# design.net
KiCad netlist of a schematic drawn in Altium Designer
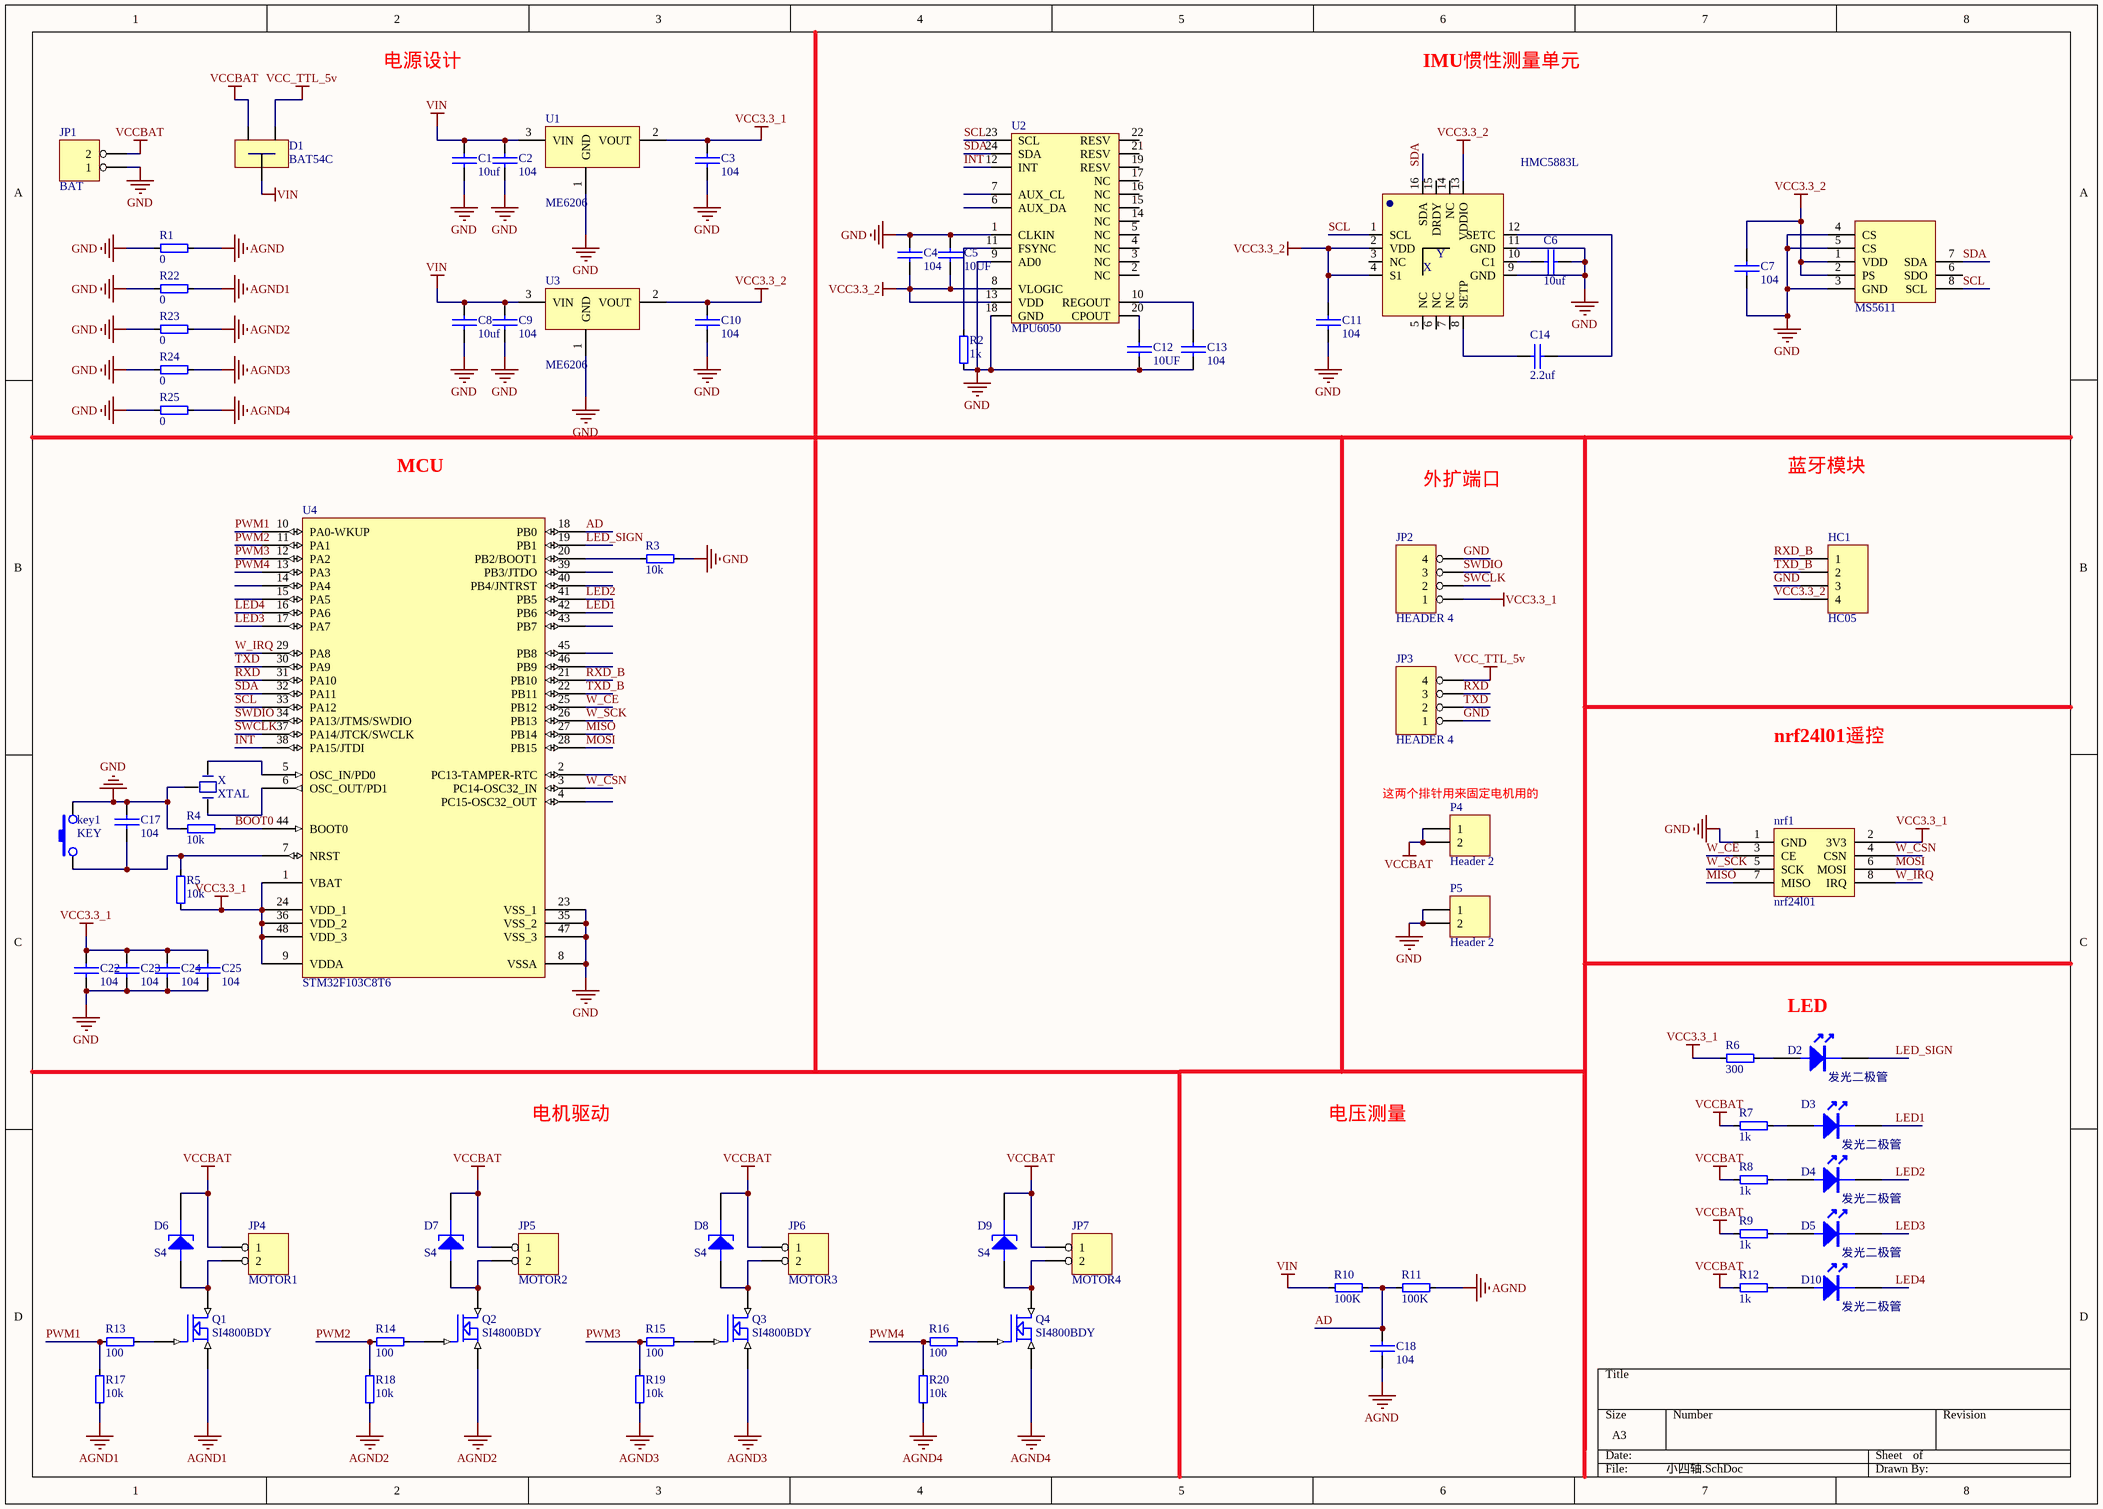
[diagram p0: 小四轴.SchDoc]

(export (version "E")
  (design (tool "Eeschema 10.0.6"))
  (components
    (comp (ref "*1") (value "HMC5883L") (footprint "hmc5883l") (libsource (lib "我的元件") (part "HMC5883L")))
    (comp (ref "arctory1") (value "MS5611") (footprint "MS5611") (libsource (lib "常用元件库") (part "MS5611")))
    (comp (ref "C1")
      (value "10uf")
      (footprint "0603P")
      (description "Capacitor")
      (libsource (lib "电容") (part "C_N"))
    )
    (comp (ref "C2")
      (value "104")
      (footprint "0603P")
      (description "Capacitor")
      (libsource (lib "电容") (part "C_N"))
    )
    (comp (ref "C3")
      (value "104")
      (footprint "0603P")
      (description "Capacitor")
      (libsource (lib "电容") (part "C_N"))
    )
    (comp (ref "C4")
      (value "104")
      (footprint "0603P")
      (description "Capacitor")
      (libsource (lib "电容") (part "C_N"))
    )
    (comp (ref "C5")
      (value "10UF")
      (footprint "0603P")
      (description "Capacitor")
      (libsource (lib "电容") (part "C_N"))
    )
    (comp (ref "C6")
      (value "10uf")
      (footprint "0603P")
      (description "Capacitor")
      (libsource (lib "电容") (part "C_N"))
    )
    (comp (ref "C7")
      (value "104")
      (footprint "0603p")
      (description "Capacitor")
      (libsource (lib "电容") (part "C_N"))
    )
    (comp (ref "C8")
      (value "10uf")
      (footprint "0603P")
      (description "Capacitor")
      (libsource (lib "电容") (part "C_N"))
    )
    (comp (ref "C9")
      (value "104")
      (footprint "0603P")
      (description "Capacitor")
      (libsource (lib "电容") (part "C_N"))
    )
    (comp (ref "C10")
      (value "104")
      (footprint "0603P")
      (description "Capacitor")
      (libsource (lib "电容") (part "C_N"))
    )
    (comp (ref "C11")
      (value "104")
      (footprint "0603P")
      (description "Capacitor")
      (libsource (lib "电容") (part "C_N"))
    )
    (comp (ref "C12")
      (value "10UF")
      (footprint "0603P")
      (description "Capacitor")
      (libsource (lib "电容") (part "C_N"))
    )
    (comp (ref "C13")
      (value "104")
      (footprint "0603P")
      (description "Capacitor")
      (libsource (lib "电容") (part "C_N"))
    )
    (comp (ref "C14")
      (value "2.2uf")
      (footprint "0603P")
      (description "Capacitor")
      (libsource (lib "电容") (part "C_N"))
    )
    (comp (ref "C17")
      (value "104")
      (footprint "0603P")
      (description "Capacitor")
      (libsource (lib "电容") (part "C_N"))
    )
    (comp (ref "C18")
      (value "104")
      (footprint "0603P")
      (description "Capacitor")
      (libsource (lib "电容") (part "C_N"))
    )
    (comp (ref "C22")
      (value "104")
      (footprint "0603P")
      (description "Capacitor")
      (libsource (lib "电容") (part "C_N"))
    )
    (comp (ref "C23")
      (value "104")
      (footprint "0603P")
      (description "Capacitor")
      (libsource (lib "电容") (part "C_N"))
    )
    (comp (ref "C24")
      (value "104")
      (footprint "0603P")
      (description "Capacitor")
      (libsource (lib "电容") (part "C_N"))
    )
    (comp (ref "C25")
      (value "104")
      (footprint "0603P")
      (description "Capacitor")
      (libsource (lib "电容") (part "C_N"))
    )
    (comp (ref "D1") (value "BAT54C") (footprint "SOT23") (libsource (lib "二极管") (part "BAT54C")))
    (comp (ref "D2") (value "发光二极管") (footprint "0805") (libsource (lib "二极管") (part "发光二极管")))
    (comp (ref "D3") (value "发光二极管") (footprint "0805") (libsource (lib "二极管") (part "发光二极管")))
    (comp (ref "D4") (value "发光二极管") (footprint "0805") (libsource (lib "二极管") (part "发光二极管")))
    (comp (ref "D5") (value "发光二极管") (footprint "0805") (libsource (lib "二极管") (part "发光二极管")))
    (comp (ref "D6")
      (value "S4")
      (footprint "LC-SOD-123")
      (description "Tunnel FDiode")
      (libsource (lib "二极管") (part "TUNNEL"))
    )
    (comp (ref "D7")
      (value "S4")
      (footprint "LC-SOD-123")
      (description "Tunnel FDiode")
      (libsource (lib "二极管") (part "TUNNEL"))
    )
    (comp (ref "D8")
      (value "S4")
      (footprint "LC-SOD-123")
      (description "Tunnel FDiode")
      (libsource (lib "二极管") (part "TUNNEL"))
    )
    (comp (ref "D9")
      (value "S4")
      (footprint "LC-SOD-123")
      (description "Tunnel FDiode")
      (libsource (lib "二极管") (part "TUNNEL"))
    )
    (comp (ref "D10") (value "发光二极管") (footprint "0805") (libsource (lib "二极管") (part "发光二极管")))
    (comp (ref "HC1")
      (value "HC05")
      (footprint "HDR1X4")
      (description "Header, 4-Pin")
      (fields (field (name "PUBLISHER") "Altium Limited"))
      (libsource (lib "Explorer STM32F407封装库") (part "Header 4"))
    )
    (comp (ref "JP1") (value "BAT") (footprint "HDR1X2") (libsource (lib "") (part "HEADER 2_1")))
    (comp (ref "JP2")
      (value "HEADER 4")
      (footprint "HDR1X4")
      (description "4 Pin Header")
      (libsource (lib "杂元件库") (part "HEADER 4"))
    )
    (comp (ref "JP3")
      (value "HEADER 4")
      (footprint "HDR1X4")
      (description "4 Pin Header")
      (libsource (lib "杂元件库") (part "HEADER 4"))
    )
    (comp (ref "JP4") (value "MOTOR1") (footprint "HDR1X2") (libsource (lib "杂元件库") (part "HEADER 2")))
    (comp (ref "JP5") (value "MOTOR2") (footprint "HDR1X2") (libsource (lib "杂元件库") (part "HEADER 2")))
    (comp (ref "JP6") (value "MOTOR3") (footprint "HDR1X2") (libsource (lib "杂元件库") (part "HEADER 2")))
    (comp (ref "JP7") (value "MOTOR4") (footprint "HDR1X2") (libsource (lib "杂元件库") (part "HEADER 2")))
    (comp (ref "key1") (value "KEY") (footprint "贴片按键6.1x3.7") (libsource (lib "常用元件库") (part "KEY")))
    (comp (ref "nrf1") (value "nrf24l01") (footprint "HDR2X4") (libsource (lib "常用元件库") (part "nrf24l01")))
    (comp (ref "P4")
      (value "Header 2")
      (footprint "HDR1X2")
      (description "Header, 2-Pin")
      (fields (field (name "PUBLISHER") "Altium Limited"))
      (libsource (lib "Miscellaneous Connectors") (part "Header 2"))
    )
    (comp (ref "P5")
      (value "Header 2")
      (footprint "HDR1X2")
      (description "Header, 2-Pin")
      (fields (field (name "PUBLISHER") "Altium Limited"))
      (libsource (lib "Miscellaneous Connectors") (part "Header 2"))
    )
    (comp (ref "Q1")
      (value "SI4800BDY")
      (footprint "LC-SOIC-8_150mil")
      (libsource (lib "Miscellaneous Devices") (part "MOSFET N"))
    )
    (comp (ref "Q2")
      (value "SI4800BDY")
      (footprint "LC-SOIC-8_150mil")
      (libsource (lib "Miscellaneous Devices") (part "MOSFET N"))
    )
    (comp (ref "Q3")
      (value "SI4800BDY")
      (footprint "LC-SOIC-8_150mil")
      (libsource (lib "Miscellaneous Devices") (part "MOSFET N"))
    )
    (comp (ref "Q4")
      (value "SI4800BDY")
      (footprint "LC-SOIC-8_150mil")
      (libsource (lib "Miscellaneous Devices") (part "MOSFET N"))
    )
    (comp (ref "R1") (value "0") (footprint "0603P") (libsource (lib "电阻") (part "RES")))
    (comp (ref "R2") (value "1k") (footprint "0603P") (libsource (lib "电阻") (part "RES")))
    (comp (ref "R3") (value "10k") (footprint "0603P") (libsource (lib "电阻") (part "RES")))
    (comp (ref "R4") (value "10k") (footprint "0603P") (libsource (lib "电阻") (part "RES")))
    (comp (ref "R5") (value "10k") (footprint "0603P") (libsource (lib "电阻") (part "RES")))
    (comp (ref "R6") (value "300") (footprint "0603P") (libsource (lib "电阻") (part "RES")))
    (comp (ref "R7") (value "1k") (footprint "0603P") (libsource (lib "电阻") (part "RES")))
    (comp (ref "R8") (value "1k") (footprint "0603P") (libsource (lib "电阻") (part "RES")))
    (comp (ref "R9") (value "1k") (footprint "0603P") (libsource (lib "电阻") (part "RES")))
    (comp (ref "R10") (value "100K") (footprint "0603P") (libsource (lib "电阻") (part "RES")))
    (comp (ref "R11") (value "100K") (footprint "0603P") (libsource (lib "电阻") (part "RES")))
    (comp (ref "R12") (value "1k") (footprint "0603P") (libsource (lib "电阻") (part "RES")))
    (comp (ref "R13") (value "100") (footprint "0603P") (libsource (lib "电阻") (part "RES")))
    (comp (ref "R14") (value "100") (footprint "0603P") (libsource (lib "电阻") (part "RES")))
    (comp (ref "R15") (value "100") (footprint "0603P") (libsource (lib "电阻") (part "RES")))
    (comp (ref "R16") (value "100") (footprint "0603P") (libsource (lib "电阻") (part "RES")))
    (comp (ref "R17") (value "10k") (footprint "0603P") (libsource (lib "电阻") (part "RES")))
    (comp (ref "R18") (value "10k") (footprint "0603P") (libsource (lib "电阻") (part "RES")))
    (comp (ref "R19") (value "10k") (footprint "0603P") (libsource (lib "电阻") (part "RES")))
    (comp (ref "R20") (value "10k") (footprint "0603P") (libsource (lib "电阻") (part "RES")))
    (comp (ref "R22") (value "0") (footprint "0603P") (libsource (lib "电阻") (part "RES")))
    (comp (ref "R23") (value "0") (footprint "0603P") (libsource (lib "电阻") (part "RES")))
    (comp (ref "R24") (value "0") (footprint "0603P") (libsource (lib "电阻") (part "RES")))
    (comp (ref "R25") (value "0") (footprint "0603P") (libsource (lib "电阻") (part "RES")))
    (comp (ref "U1") (value "ME6206") (footprint "ME6206") (libsource (lib "我的元件") (part "ME6206")))
    (comp (ref "U2")
      (value "MPU6050")
      (footprint "QFN24")
      (description "9轴运动处理传感器")
      (libsource (lib "Explorer STM32F407封装库") (part "MPU6050"))
    )
    (comp (ref "U3") (value "ME6206") (footprint "ME6206") (libsource (lib "我的元件") (part "ME6206")))
    (comp (ref "U4")
      (value "STM32F103C8T6")
      (footprint "LQFP48_N")
      (description "STM32 ARM-based 32-bit MCU with 64 Kbytes Flash, 48-pin LQFP, Industrial Temperature")
      (fields (field (name "PUBLISHER") "*"))
      (libsource (lib "STM32 SCH") (part "STM32F103C8T6"))
    )
    (comp (ref "X") (value "XTAL") (footprint "三脚晶振") (libsource (lib "常用元件库") (part "XTAL_3P")))
  )
  (nets
    (net (code "1") (name "/AD") (class "Default")
      (node (ref "C18") (pin "2") (pinfunction "2_2") (pintype "passive"))
      (node (ref "R10") (pin "1") (pinfunction "1_1") (pintype "passive"))
      (node (ref "R11") (pin "2") (pinfunction "2_2") (pintype "passive"))
      (node (ref "U4") (pin "18") (pinfunction "PB0_18") (pintype "bidirectional"))
    )
    (net (code "2") (name "/BOOT0") (class "Default")
      (node (ref "R4") (pin "2") (pinfunction "2_2") (pintype "passive"))
      (node (ref "U4") (pin "44") (pinfunction "BOOT0_44") (pintype "input"))
    )
    (net (code "3") (name "/INT") (class "Default")
      (node (ref "U2") (pin "12") (pinfunction "INT_12") (pintype "passive"))
      (node (ref "U4") (pin "38") (pinfunction "PA15/JTDI_38") (pintype "bidirectional"))
    )
    (net (code "4") (name "/LED1") (class "Default")
      (node (ref "D3") (pin "2") (pinfunction "2_2") (pintype "passive"))
      (node (ref "U4") (pin "42") (pinfunction "PB6_42") (pintype "bidirectional"))
    )
    (net (code "5") (name "/LED2") (class "Default")
      (node (ref "D4") (pin "2") (pinfunction "2_2") (pintype "passive"))
      (node (ref "U4") (pin "41") (pinfunction "PB5_41") (pintype "bidirectional"))
    )
    (net (code "6") (name "/LED3") (class "Default")
      (node (ref "D5") (pin "2") (pinfunction "2_2") (pintype "passive"))
      (node (ref "U4") (pin "17") (pinfunction "PA7_17") (pintype "bidirectional"))
    )
    (net (code "7") (name "/LED4") (class "Default")
      (node (ref "D10") (pin "2") (pinfunction "2_2") (pintype "passive"))
      (node (ref "U4") (pin "16") (pinfunction "PA6_16") (pintype "bidirectional"))
    )
    (net (code "8") (name "/LED_SIGN") (class "Default")
      (node (ref "D2") (pin "2") (pinfunction "2_2") (pintype "passive"))
      (node (ref "U4") (pin "19") (pinfunction "PB1_19") (pintype "bidirectional"))
    )
    (net (code "9") (name "/MISO") (class "Default")
      (node (ref "U4") (pin "27") (pinfunction "PB14_27") (pintype "bidirectional"))
      (node (ref "nrf1") (pin "7") (pinfunction "MISO_7") (pintype "passive"))
    )
    (net (code "10") (name "/MOSI") (class "Default")
      (node (ref "U4") (pin "28") (pinfunction "PB15_28") (pintype "bidirectional"))
      (node (ref "nrf1") (pin "6") (pinfunction "MOSI_6") (pintype "passive"))
    )
    (net (code "11") (name "/PWM1") (class "Default")
      (node (ref "R13") (pin "2") (pinfunction "2_2") (pintype "passive"))
      (node (ref "R17") (pin "1") (pinfunction "1_1") (pintype "passive"))
      (node (ref "U4") (pin "10") (pinfunction "PA0-WKUP_10") (pintype "bidirectional"))
    )
    (net (code "12") (name "/PWM2") (class "Default")
      (node (ref "R14") (pin "2") (pinfunction "2_2") (pintype "passive"))
      (node (ref "R18") (pin "1") (pinfunction "1_1") (pintype "passive"))
      (node (ref "U4") (pin "11") (pinfunction "PA1_11") (pintype "bidirectional"))
    )
    (net (code "13") (name "/PWM3") (class "Default")
      (node (ref "R15") (pin "2") (pinfunction "2_2") (pintype "passive"))
      (node (ref "R19") (pin "1") (pinfunction "1_1") (pintype "passive"))
      (node (ref "U4") (pin "12") (pinfunction "PA2_12") (pintype "bidirectional"))
    )
    (net (code "14") (name "/PWM4") (class "Default")
      (node (ref "R16") (pin "2") (pinfunction "2_2") (pintype "passive"))
      (node (ref "R20") (pin "1") (pinfunction "1_1") (pintype "passive"))
      (node (ref "U4") (pin "13") (pinfunction "PA3_13") (pintype "bidirectional"))
    )
    (net (code "15") (name "/RXD") (class "Default")
      (node (ref "JP3") (pin "3") (pinfunction "3_3") (pintype "passive"))
      (node (ref "U4") (pin "31") (pinfunction "PA10_31") (pintype "bidirectional"))
    )
    (net (code "16") (name "/RXD_B") (class "Default")
      (node (ref "HC1") (pin "1") (pinfunction "1_1") (pintype "passive"))
      (node (ref "U4") (pin "21") (pinfunction "PB10_21") (pintype "bidirectional"))
    )
    (net (code "17") (name "/SCL") (class "Default")
      (node (ref "*1") (pin "1") (pinfunction "SCL_1") (pintype "passive"))
      (node (ref "U2") (pin "23") (pinfunction "SCL_23") (pintype "passive"))
      (node (ref "U4") (pin "33") (pinfunction "PA12_33") (pintype "bidirectional"))
      (node (ref "arctory1") (pin "8") (pinfunction "SCL_8") (pintype "passive"))
    )
    (net (code "18") (name "/SDA") (class "Default")
      (node (ref "*1") (pin "16") (pinfunction "SDA_16") (pintype "passive"))
      (node (ref "U2") (pin "24") (pinfunction "SDA_24") (pintype "passive"))
      (node (ref "U4") (pin "32") (pinfunction "PA11_32") (pintype "bidirectional"))
      (node (ref "arctory1") (pin "7") (pinfunction "SDA_7") (pintype "passive"))
    )
    (net (code "19") (name "/SWCLK") (class "Default")
      (node (ref "JP2") (pin "2") (pinfunction "2_2") (pintype "passive"))
      (node (ref "U4") (pin "37") (pinfunction "PA14/JTCK/SWCLK_37") (pintype "bidirectional"))
    )
    (net (code "20") (name "/SWDIO") (class "Default")
      (node (ref "JP2") (pin "3") (pinfunction "3_3") (pintype "passive"))
      (node (ref "U4") (pin "34") (pinfunction "PA13/JTMS/SWDIO_34") (pintype "bidirectional"))
    )
    (net (code "21") (name "/TXD") (class "Default")
      (node (ref "JP3") (pin "2") (pinfunction "2_2") (pintype "passive"))
      (node (ref "U4") (pin "30") (pinfunction "PA9_30") (pintype "bidirectional"))
    )
    (net (code "22") (name "/TXD_B") (class "Default")
      (node (ref "HC1") (pin "2") (pinfunction "2_2") (pintype "passive"))
      (node (ref "U4") (pin "22") (pinfunction "PB11_22") (pintype "bidirectional"))
    )
    (net (code "23") (name "/W_CE") (class "Default")
      (node (ref "U4") (pin "25") (pinfunction "PB12_25") (pintype "bidirectional"))
      (node (ref "nrf1") (pin "3") (pinfunction "CE_3") (pintype "passive"))
    )
    (net (code "24") (name "/W_CSN") (class "Default")
      (node (ref "U4") (pin "3") (pinfunction "PC14-OSC32_IN_3") (pintype "bidirectional"))
      (node (ref "nrf1") (pin "4") (pinfunction "CSN_4") (pintype "passive"))
    )
    (net (code "25") (name "/W_IRQ") (class "Default")
      (node (ref "U4") (pin "29") (pinfunction "PA8_29") (pintype "bidirectional"))
      (node (ref "nrf1") (pin "8") (pinfunction "IRQ_8") (pintype "passive"))
    )
    (net (code "26") (name "/W_SCK") (class "Default")
      (node (ref "U4") (pin "26") (pinfunction "PB13_26") (pintype "bidirectional"))
      (node (ref "nrf1") (pin "5") (pinfunction "SCK_5") (pintype "passive"))
    )
    (net (code "27") (name "AGND") (class "Default")
      (node (ref "C18") (pin "1") (pinfunction "1_1") (pintype "passive"))
      (node (ref "R1") (pin "1") (pinfunction "1_1") (pintype "passive"))
      (node (ref "R11") (pin "1") (pinfunction "1_1") (pintype "passive"))
    )
    (net (code "28") (name "AGND1") (class "Default")
      (node (ref "Q1") (pin "3") (pinfunction "S_3") (pintype "input"))
      (node (ref "R17") (pin "2") (pinfunction "2_2") (pintype "passive"))
      (node (ref "R22") (pin "1") (pinfunction "1_1") (pintype "passive"))
    )
    (net (code "29") (name "AGND2") (class "Default")
      (node (ref "Q2") (pin "3") (pinfunction "S_3") (pintype "input"))
      (node (ref "R18") (pin "2") (pinfunction "2_2") (pintype "passive"))
      (node (ref "R23") (pin "1") (pinfunction "1_1") (pintype "passive"))
    )
    (net (code "30") (name "AGND3") (class "Default")
      (node (ref "Q3") (pin "3") (pinfunction "S_3") (pintype "input"))
      (node (ref "R19") (pin "2") (pinfunction "2_2") (pintype "passive"))
      (node (ref "R24") (pin "1") (pinfunction "1_1") (pintype "passive"))
    )
    (net (code "31") (name "AGND4") (class "Default")
      (node (ref "Q4") (pin "3") (pinfunction "S_3") (pintype "input"))
      (node (ref "R20") (pin "2") (pinfunction "2_2") (pintype "passive"))
      (node (ref "R25") (pin "1") (pinfunction "1_1") (pintype "passive"))
    )
    (net (code "32") (name "GND") (class "Default")
      (node (ref "*1") (pin "11") (pinfunction "GND_11") (pintype "passive"))
      (node (ref "*1") (pin "9") (pinfunction "GND_9") (pintype "passive"))
      (node (ref "C1") (pin "1") (pinfunction "1_1") (pintype "passive"))
      (node (ref "C10") (pin "1") (pinfunction "1_1") (pintype "passive"))
      (node (ref "C11") (pin "2") (pinfunction "2_2") (pintype "passive"))
      (node (ref "C12") (pin "1") (pinfunction "1_1") (pintype "passive"))
      (node (ref "C13") (pin "2") (pinfunction "2_2") (pintype "passive"))
      (node (ref "C17") (pin "1") (pinfunction "1_1") (pintype "passive"))
      (node (ref "C2") (pin "1") (pinfunction "1_1") (pintype "passive"))
      (node (ref "C22") (pin "1") (pinfunction "1_1") (pintype "passive"))
      (node (ref "C23") (pin "1") (pinfunction "1_1") (pintype "passive"))
      (node (ref "C24") (pin "1") (pinfunction "1_1") (pintype "passive"))
      (node (ref "C25") (pin "1") (pinfunction "1_1") (pintype "passive"))
      (node (ref "C3") (pin "1") (pinfunction "1_1") (pintype "passive"))
      (node (ref "C4") (pin "1") (pinfunction "1_1") (pintype "passive"))
      (node (ref "C5") (pin "2") (pinfunction "2_2") (pintype "passive"))
      (node (ref "C6") (pin "2") (pinfunction "2_2") (pintype "passive"))
      (node (ref "C7") (pin "2") (pinfunction "2_2") (pintype "passive"))
      (node (ref "C8") (pin "1") (pinfunction "1_1") (pintype "passive"))
      (node (ref "C9") (pin "1") (pinfunction "1_1") (pintype "passive"))
      (node (ref "HC1") (pin "3") (pinfunction "3_3") (pintype "passive"))
      (node (ref "JP1") (pin "1") (pinfunction "1_1") (pintype "passive"))
      (node (ref "JP2") (pin "4") (pinfunction "4_4") (pintype "passive"))
      (node (ref "JP3") (pin "1") (pinfunction "1_1") (pintype "passive"))
      (node (ref "P5") (pin "1") (pinfunction "1_1") (pintype "passive"))
      (node (ref "P5") (pin "2") (pinfunction "2_2") (pintype "passive"))
      (node (ref "R1") (pin "2") (pinfunction "2_2") (pintype "passive"))
      (node (ref "R2") (pin "1") (pinfunction "1_1") (pintype "passive"))
      (node (ref "R22") (pin "2") (pinfunction "2_2") (pintype "passive"))
      (node (ref "R23") (pin "2") (pinfunction "2_2") (pintype "passive"))
      (node (ref "R24") (pin "2") (pinfunction "2_2") (pintype "passive"))
      (node (ref "R25") (pin "2") (pinfunction "2_2") (pintype "passive"))
      (node (ref "R3") (pin "1") (pinfunction "1_1") (pintype "passive"))
      (node (ref "R4") (pin "1") (pinfunction "1_1") (pintype "passive"))
      (node (ref "U1") (pin "1") (pinfunction "GND_1") (pintype "passive"))
      (node (ref "U2") (pin "1") (pinfunction "CLKIN_1") (pintype "passive"))
      (node (ref "U2") (pin "18") (pinfunction "GND_18") (pintype "passive"))
      (node (ref "U2") (pin "9") (pinfunction "AD0_9") (pintype "passive"))
      (node (ref "U3") (pin "1") (pinfunction "GND_1") (pintype "passive"))
      (node (ref "U4") (pin "23") (pinfunction "VSS_1_23") (pintype "power_in"))
      (node (ref "U4") (pin "35") (pinfunction "VSS_2_35") (pintype "power_in"))
      (node (ref "U4") (pin "47") (pinfunction "VSS_3_47") (pintype "power_in"))
      (node (ref "U4") (pin "8") (pinfunction "VSSA_8") (pintype "power_in"))
      (node (ref "X") (pin "3") (pinfunction "3_3") (pintype "passive"))
      (node (ref "arctory1") (pin "3") (pinfunction "GND_3") (pintype "passive"))
      (node (ref "arctory1") (pin "4") (pinfunction "CS_4") (pintype "passive"))
      (node (ref "arctory1") (pin "5") (pinfunction "CS_5") (pintype "passive"))
      (node (ref "key1") (pin "2") (pinfunction "2_2") (pintype "passive"))
      (node (ref "nrf1") (pin "1") (pinfunction "GND_1") (pintype "passive"))
    )
    (net (code "33") (name "Net-(*1-C1)") (class "Default")
      (node (ref "*1") (pin "10") (pinfunction "C1_10") (pintype "passive"))
      (node (ref "C6") (pin "1") (pinfunction "1_1") (pintype "passive"))
    )
    (net (code "34") (name "Net-(*1-SETC)") (class "Default")
      (node (ref "*1") (pin "12") (pinfunction "SETC_12") (pintype "passive"))
      (node (ref "C14") (pin "2") (pinfunction "2_2") (pintype "passive"))
    )
    (net (code "35") (name "Net-(*1-SETP)") (class "Default")
      (node (ref "*1") (pin "8") (pinfunction "SETP_8") (pintype "passive"))
      (node (ref "C14") (pin "1") (pinfunction "1_1") (pintype "passive"))
    )
    (net (code "36") (name "Net-(D2-Pad1)") (class "Default")
      (node (ref "D2") (pin "1") (pinfunction "1_1") (pintype "passive"))
      (node (ref "R6") (pin "1") (pinfunction "1_1") (pintype "passive"))
    )
    (net (code "37") (name "Net-(D3-Pad1)") (class "Default")
      (node (ref "D3") (pin "1") (pinfunction "1_1") (pintype "passive"))
      (node (ref "R7") (pin "1") (pinfunction "1_1") (pintype "passive"))
    )
    (net (code "38") (name "Net-(D4-Pad1)") (class "Default")
      (node (ref "D4") (pin "1") (pinfunction "1_1") (pintype "passive"))
      (node (ref "R8") (pin "1") (pinfunction "1_1") (pintype "passive"))
    )
    (net (code "39") (name "Net-(D5-Pad1)") (class "Default")
      (node (ref "D5") (pin "1") (pinfunction "1_1") (pintype "passive"))
      (node (ref "R9") (pin "1") (pinfunction "1_1") (pintype "passive"))
    )
    (net (code "40") (name "Net-(D6-A)") (class "Default")
      (node (ref "D6") (pin "1") (pinfunction "A_1") (pintype "passive"))
      (node (ref "JP4") (pin "2") (pinfunction "2_2") (pintype "passive"))
      (node (ref "Q1") (pin "2") (pinfunction "D_2") (pintype "input"))
    )
    (net (code "41") (name "Net-(D7-A)") (class "Default")
      (node (ref "D7") (pin "1") (pinfunction "A_1") (pintype "passive"))
      (node (ref "JP5") (pin "2") (pinfunction "2_2") (pintype "passive"))
      (node (ref "Q2") (pin "2") (pinfunction "D_2") (pintype "input"))
    )
    (net (code "42") (name "Net-(D8-A)") (class "Default")
      (node (ref "D8") (pin "1") (pinfunction "A_1") (pintype "passive"))
      (node (ref "JP6") (pin "2") (pinfunction "2_2") (pintype "passive"))
      (node (ref "Q3") (pin "2") (pinfunction "D_2") (pintype "input"))
    )
    (net (code "43") (name "Net-(D9-A)") (class "Default")
      (node (ref "D9") (pin "1") (pinfunction "A_1") (pintype "passive"))
      (node (ref "JP7") (pin "2") (pinfunction "2_2") (pintype "passive"))
      (node (ref "Q4") (pin "2") (pinfunction "D_2") (pintype "input"))
    )
    (net (code "44") (name "Net-(D10-Pad1)") (class "Default")
      (node (ref "D10") (pin "1") (pinfunction "1_1") (pintype "passive"))
      (node (ref "R12") (pin "1") (pinfunction "1_1") (pintype "passive"))
    )
    (net (code "45") (name "Net-(Q1-G)") (class "Default")
      (node (ref "Q1") (pin "1") (pinfunction "G_1") (pintype "input"))
      (node (ref "R13") (pin "1") (pinfunction "1_1") (pintype "passive"))
    )
    (net (code "46") (name "Net-(Q2-G)") (class "Default")
      (node (ref "Q2") (pin "1") (pinfunction "G_1") (pintype "input"))
      (node (ref "R14") (pin "1") (pinfunction "1_1") (pintype "passive"))
    )
    (net (code "47") (name "Net-(Q3-G)") (class "Default")
      (node (ref "Q3") (pin "1") (pinfunction "G_1") (pintype "input"))
      (node (ref "R15") (pin "1") (pinfunction "1_1") (pintype "passive"))
    )
    (net (code "48") (name "Net-(Q4-G)") (class "Default")
      (node (ref "Q4") (pin "1") (pinfunction "G_1") (pintype "input"))
      (node (ref "R16") (pin "1") (pinfunction "1_1") (pintype "passive"))
    )
    (net (code "49") (name "Net-(U2-CPOUT)") (class "Default")
      (node (ref "C12") (pin "2") (pinfunction "2_2") (pintype "passive"))
      (node (ref "U2") (pin "20") (pinfunction "CPOUT_20") (pintype "passive"))
    )
    (net (code "50") (name "Net-(U2-FSYNC)") (class "Default")
      (node (ref "R2") (pin "2") (pinfunction "2_2") (pintype "passive"))
      (node (ref "U2") (pin "11") (pinfunction "FSYNC_11") (pintype "passive"))
    )
    (net (code "51") (name "Net-(U2-REGOUT)") (class "Default")
      (node (ref "C13") (pin "1") (pinfunction "1_1") (pintype "passive"))
      (node (ref "U2") (pin "10") (pinfunction "REGOUT_10") (pintype "passive"))
    )
    (net (code "52") (name "Net-(U4-NRST)") (class "Default")
      (node (ref "C17") (pin "2") (pinfunction "2_2") (pintype "passive"))
      (node (ref "R5") (pin "1") (pinfunction "1_1") (pintype "passive"))
      (node (ref "U4") (pin "7") (pinfunction "NRST_7") (pintype "bidirectional"))
      (node (ref "key1") (pin "1") (pinfunction "1_1") (pintype "passive"))
    )
    (net (code "53") (name "Net-(U4-OSC_IN{slash}PD0)") (class "Default")
      (node (ref "U4") (pin "5") (pinfunction "OSC_IN/PD0_5") (pintype "input"))
      (node (ref "X") (pin "1") (pinfunction "1_1") (pintype "passive"))
    )
    (net (code "54") (name "Net-(U4-OSC_OUT{slash}PD1)") (class "Default")
      (node (ref "U4") (pin "6") (pinfunction "OSC_OUT/PD1_6") (pintype "output"))
      (node (ref "X") (pin "2") (pinfunction "2_2") (pintype "passive"))
    )
    (net (code "55") (name "Net-(U4-PB2{slash}BOOT1)") (class "Default")
      (node (ref "R3") (pin "2") (pinfunction "2_2") (pintype "passive"))
      (node (ref "U4") (pin "20") (pinfunction "PB2/BOOT1_20") (pintype "bidirectional"))
    )
    (net (code "56") (name "VCC3.3_1") (class "Default")
      (node (ref "C22") (pin "2") (pinfunction "2_2") (pintype "passive"))
      (node (ref "C23") (pin "2") (pinfunction "2_2") (pintype "passive"))
      (node (ref "C24") (pin "2") (pinfunction "2_2") (pintype "passive"))
      (node (ref "C25") (pin "2") (pinfunction "2_2") (pintype "passive"))
      (node (ref "C3") (pin "2") (pinfunction "2_2") (pintype "passive"))
      (node (ref "JP2") (pin "1") (pinfunction "1_1") (pintype "passive"))
      (node (ref "R5") (pin "2") (pinfunction "2_2") (pintype "passive"))
      (node (ref "R6") (pin "2") (pinfunction "2_2") (pintype "passive"))
      (node (ref "U1") (pin "2") (pinfunction "VOUT_2") (pintype "passive"))
      (node (ref "U4") (pin "1") (pinfunction "VBAT_1") (pintype "power_in"))
      (node (ref "U4") (pin "24") (pinfunction "VDD_1_24") (pintype "power_in"))
      (node (ref "U4") (pin "36") (pinfunction "VDD_2_36") (pintype "power_in"))
      (node (ref "U4") (pin "48") (pinfunction "VDD_3_48") (pintype "power_in"))
      (node (ref "U4") (pin "9") (pinfunction "VDDA_9") (pintype "power_in"))
      (node (ref "nrf1") (pin "2") (pinfunction "3V3_2") (pintype "passive"))
    )
    (net (code "57") (name "VCC3.3_2") (class "Default")
      (node (ref "*1") (pin "13") (pinfunction "VDDIO_13") (pintype "passive"))
      (node (ref "*1") (pin "2") (pinfunction "VDD_2") (pintype "passive"))
      (node (ref "*1") (pin "4") (pinfunction "S1_4") (pintype "passive"))
      (node (ref "C10") (pin "2") (pinfunction "2_2") (pintype "passive"))
      (node (ref "C11") (pin "1") (pinfunction "1_1") (pintype "passive"))
      (node (ref "C4") (pin "2") (pinfunction "2_2") (pintype "passive"))
      (node (ref "C5") (pin "1") (pinfunction "1_1") (pintype "passive"))
      (node (ref "C7") (pin "1") (pinfunction "1_1") (pintype "passive"))
      (node (ref "HC1") (pin "4") (pinfunction "4_4") (pintype "passive"))
      (node (ref "U2") (pin "13") (pinfunction "VDD_13") (pintype "passive"))
      (node (ref "U2") (pin "8") (pinfunction "VLOGIC_8") (pintype "passive"))
      (node (ref "U3") (pin "2") (pinfunction "VOUT_2") (pintype "passive"))
      (node (ref "arctory1") (pin "1") (pinfunction "VDD_1") (pintype "passive"))
      (node (ref "arctory1") (pin "2") (pinfunction "PS_2") (pintype "passive"))
    )
    (net (code "58") (name "VCCBAT") (class "Default")
      (node (ref "D1") (pin "E") (pinfunction "3_E") (pintype "passive"))
      (node (ref "D6") (pin "2") (pinfunction "K_2") (pintype "passive"))
      (node (ref "D7") (pin "2") (pinfunction "K_2") (pintype "passive"))
      (node (ref "D8") (pin "2") (pinfunction "K_2") (pintype "passive"))
      (node (ref "D9") (pin "2") (pinfunction "K_2") (pintype "passive"))
      (node (ref "JP1") (pin "2") (pinfunction "2_2") (pintype "passive"))
      (node (ref "JP4") (pin "1") (pinfunction "1_1") (pintype "passive"))
      (node (ref "JP5") (pin "1") (pinfunction "1_1") (pintype "passive"))
      (node (ref "JP6") (pin "1") (pinfunction "1_1") (pintype "passive"))
      (node (ref "JP7") (pin "1") (pinfunction "1_1") (pintype "passive"))
      (node (ref "P4") (pin "1") (pinfunction "1_1") (pintype "passive"))
      (node (ref "P4") (pin "2") (pinfunction "2_2") (pintype "passive"))
      (node (ref "R12") (pin "2") (pinfunction "2_2") (pintype "passive"))
      (node (ref "R7") (pin "2") (pinfunction "2_2") (pintype "passive"))
      (node (ref "R8") (pin "2") (pinfunction "2_2") (pintype "passive"))
      (node (ref "R9") (pin "2") (pinfunction "2_2") (pintype "passive"))
    )
    (net (code "59") (name "VCC_TTL_5v") (class "Default")
      (node (ref "D1") (pin "B") (pinfunction "2_B") (pintype "passive"))
      (node (ref "JP3") (pin "4") (pinfunction "4_4") (pintype "passive"))
    )
    (net (code "60") (name "VIN") (class "Default")
      (node (ref "C1") (pin "2") (pinfunction "2_2") (pintype "passive"))
      (node (ref "C2") (pin "2") (pinfunction "2_2") (pintype "passive"))
      (node (ref "C8") (pin "2") (pinfunction "2_2") (pintype "passive"))
      (node (ref "C9") (pin "2") (pinfunction "2_2") (pintype "passive"))
      (node (ref "D1") (pin "C") (pinfunction "1_C") (pintype "passive"))
      (node (ref "R10") (pin "2") (pinfunction "2_2") (pintype "passive"))
      (node (ref "U1") (pin "3") (pinfunction "VIN_3") (pintype "passive"))
      (node (ref "U3") (pin "3") (pinfunction "VIN_3") (pintype "passive"))
    )
    (net (code "61") (name "unconnected-(*1-DRDY-Pad15)") (class "Default")
      (node (ref "*1") (pin "15") (pinfunction "DRDY_15") (pintype "passive"))
    )
    (net (code "62") (name "unconnected-(*1-NC-Pad3)") (class "Default")
      (node (ref "*1") (pin "3") (pinfunction "NC_3") (pintype "passive"))
    )
    (net (code "63") (name "unconnected-(*1-NC-Pad5)") (class "Default")
      (node (ref "*1") (pin "5") (pinfunction "NC_5") (pintype "passive"))
    )
    (net (code "64") (name "unconnected-(*1-NC-Pad6)") (class "Default")
      (node (ref "*1") (pin "6") (pinfunction "NC_6") (pintype "passive"))
    )
    (net (code "65") (name "unconnected-(*1-NC-Pad7)") (class "Default")
      (node (ref "*1") (pin "7") (pinfunction "NC_7") (pintype "passive"))
    )
    (net (code "66") (name "unconnected-(*1-NC-Pad14)") (class "Default")
      (node (ref "*1") (pin "14") (pinfunction "NC_14") (pintype "passive"))
    )
    (net (code "67") (name "unconnected-(U2-AUX_CL-Pad7)") (class "Default")
      (node (ref "U2") (pin "7") (pinfunction "AUX_CL_7") (pintype "passive"))
    )
    (net (code "68") (name "unconnected-(U2-AUX_DA-Pad6)") (class "Default")
      (node (ref "U2") (pin "6") (pinfunction "AUX_DA_6") (pintype "passive"))
    )
    (net (code "69") (name "unconnected-(U2-NC-Pad2)") (class "Default")
      (node (ref "U2") (pin "2") (pinfunction "NC_2") (pintype "passive"))
    )
    (net (code "70") (name "unconnected-(U2-NC-Pad3)") (class "Default")
      (node (ref "U2") (pin "3") (pinfunction "NC_3") (pintype "passive"))
    )
    (net (code "71") (name "unconnected-(U2-NC-Pad4)") (class "Default")
      (node (ref "U2") (pin "4") (pinfunction "NC_4") (pintype "passive"))
    )
    (net (code "72") (name "unconnected-(U2-NC-Pad5)") (class "Default")
      (node (ref "U2") (pin "5") (pinfunction "NC_5") (pintype "passive"))
    )
    (net (code "73") (name "unconnected-(U2-NC-Pad14)") (class "Default")
      (node (ref "U2") (pin "14") (pinfunction "NC_14") (pintype "passive"))
    )
    (net (code "74") (name "unconnected-(U2-NC-Pad15)") (class "Default")
      (node (ref "U2") (pin "15") (pinfunction "NC_15") (pintype "passive"))
    )
    (net (code "75") (name "unconnected-(U2-NC-Pad16)") (class "Default")
      (node (ref "U2") (pin "16") (pinfunction "NC_16") (pintype "passive"))
    )
    (net (code "76") (name "unconnected-(U2-NC-Pad17)") (class "Default")
      (node (ref "U2") (pin "17") (pinfunction "NC_17") (pintype "passive"))
    )
    (net (code "77") (name "unconnected-(U2-RESV-Pad19)") (class "Default")
      (node (ref "U2") (pin "19") (pinfunction "RESV_19") (pintype "passive"))
    )
    (net (code "78") (name "unconnected-(U2-RESV-Pad21)") (class "Default")
      (node (ref "U2") (pin "21") (pinfunction "RESV_21") (pintype "passive"))
    )
    (net (code "79") (name "unconnected-(U2-RESV-Pad22)") (class "Default")
      (node (ref "U2") (pin "22") (pinfunction "RESV_22") (pintype "passive"))
    )
    (net (code "80") (name "unconnected-(U4-PA4-Pad14)") (class "Default")
      (node (ref "U4") (pin "14") (pinfunction "PA4_14") (pintype "bidirectional"))
    )
    (net (code "81") (name "unconnected-(U4-PA5-Pad15)") (class "Default")
      (node (ref "U4") (pin "15") (pinfunction "PA5_15") (pintype "bidirectional"))
    )
    (net (code "82") (name "unconnected-(U4-PB3{slash}JTDO-Pad39)") (class "Default")
      (node (ref "U4") (pin "39") (pinfunction "PB3/JTDO_39") (pintype "bidirectional"))
    )
    (net (code "83") (name "unconnected-(U4-PB4{slash}JNTRST-Pad40)") (class "Default")
      (node (ref "U4") (pin "40") (pinfunction "PB4/JNTRST_40") (pintype "bidirectional"))
    )
    (net (code "84") (name "unconnected-(U4-PB7-Pad43)") (class "Default")
      (node (ref "U4") (pin "43") (pinfunction "PB7_43") (pintype "bidirectional"))
    )
    (net (code "85") (name "unconnected-(U4-PB8-Pad45)") (class "Default")
      (node (ref "U4") (pin "45") (pinfunction "PB8_45") (pintype "bidirectional"))
    )
    (net (code "86") (name "unconnected-(U4-PB9-Pad46)") (class "Default")
      (node (ref "U4") (pin "46") (pinfunction "PB9_46") (pintype "bidirectional"))
    )
    (net (code "87") (name "unconnected-(U4-PC13-TAMPER-RTC-Pad2)") (class "Default")
      (node (ref "U4") (pin "2") (pinfunction "PC13-TAMPER-RTC_2") (pintype "bidirectional"))
    )
    (net (code "88") (name "unconnected-(U4-PC15-OSC32_OUT-Pad4)") (class "Default")
      (node (ref "U4") (pin "4") (pinfunction "PC15-OSC32_OUT_4") (pintype "bidirectional"))
    )
    (net (code "89") (name "unconnected-(arctory1-SDO-Pad6)") (class "Default")
      (node (ref "arctory1") (pin "6") (pinfunction "SDO_6") (pintype "passive"))
    )
  )
)
